# MICS-4514_CO_and_NOx_Sensor_Breakout.net
KiCad netlist of a schematic drawn in EAGLE
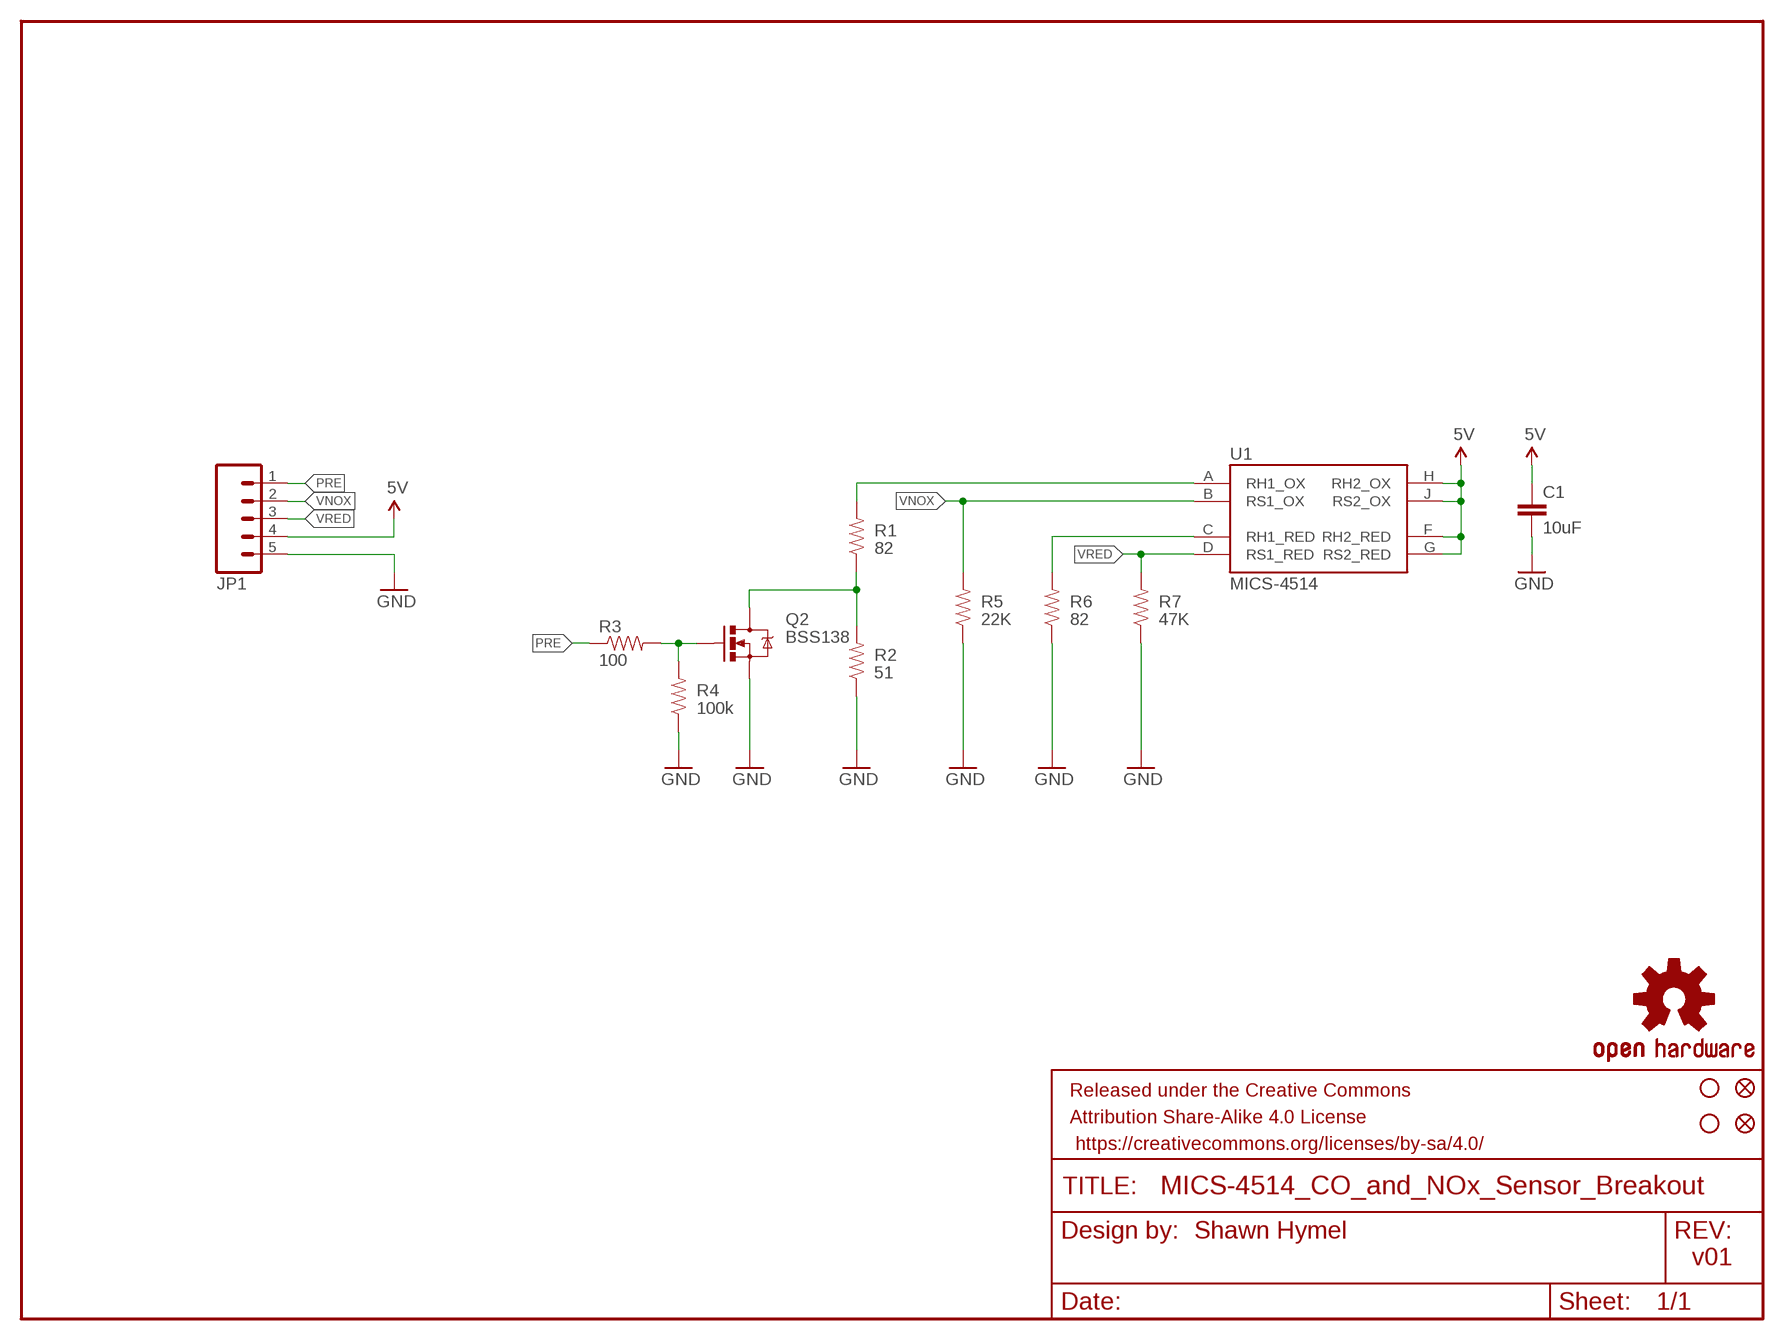
[diagram p0: schematic, sheet 1]

(export (version "E")
  (design (tool "Eeschema 10.0.6"))
  (components
    (comp (ref "C1")
      (value "10uF")
      (footprint "eagle-import:0805")
      (libsource (lib "eagle-import") (part "CAP0805"))
    )
    (comp (ref "FID1")
      (value "FIDUCIAL1X2")
      (footprint "eagle-import:FIDUCIAL-1X2")
      (libsource (lib "eagle-import") (part "FIDUCIAL1X2"))
    )
    (comp (ref "FID2")
      (value "FIDUCIAL1X2")
      (footprint "eagle-import:FIDUCIAL-1X2")
      (libsource (lib "eagle-import") (part "FIDUCIAL1X2"))
    )
    (comp (ref "FRAME1")
      (value "FRAME-LETTER")
      (footprint "eagle-import:CREATIVE_COMMONS")
      (libsource (lib "eagle-import") (part "FRAME-LETTER"))
    )
    (comp (ref "JP1")
      (value "M05LOCK")
      (footprint "eagle-import:1X05_LOCK")
      (libsource (lib "eagle-import") (part "M05LOCK"))
    )
    (comp (ref "LOGO1")
      (value "OSHW-LOGOS")
      (footprint "eagle-import:OSHW-LOGO-S")
      (libsource (lib "eagle-import") (part "OSHW-LOGOS"))
    )
    (comp (ref "Q2")
      (value "MOSFET-NCHANNELBSS138")
      (footprint "eagle-import:SOT23-3")
      (fields (field (name "P_NAME") "BSS138"))
      (libsource (lib "eagle-import") (part "MOSFET-NCHANNELBSS138"))
    )
    (comp (ref "R1")
      (value "82")
      (footprint "eagle-import:0805")
      (libsource (lib "eagle-import") (part "RESISTOR0805-RES"))
    )
    (comp (ref "R2")
      (value "51")
      (footprint "eagle-import:0603-RES")
      (libsource (lib "eagle-import") (part "RESISTOR0603"))
    )
    (comp (ref "R3")
      (value "100")
      (footprint "eagle-import:0603-RES")
      (libsource (lib "eagle-import") (part "100OHM1/10W1%(0603)"))
    )
    (comp (ref "R4")
      (value "100k")
      (footprint "eagle-import:0603-RES")
      (libsource (lib "eagle-import") (part "100KOHM1/10W1%(0603)"))
    )
    (comp (ref "R5")
      (value "22K")
      (footprint "eagle-import:0603-RES")
      (libsource (lib "eagle-import") (part "22KOHM1/10W1%(0603)"))
    )
    (comp (ref "R6")
      (value "82")
      (footprint "eagle-import:0805")
      (libsource (lib "eagle-import") (part "RESISTOR0805-RES"))
    )
    (comp (ref "R7")
      (value "47K")
      (footprint "eagle-import:0603-RES")
      (libsource (lib "eagle-import") (part "47KOHM1/10W1%(0603)"))
    )
    (comp (ref "STANDOFF3")
      (value "STAND-OFF")
      (footprint "eagle-import:STAND-OFF")
      (libsource (lib "eagle-import") (part "STAND-OFF"))
    )
    (comp (ref "STANDOFF5")
      (value "STAND-OFF")
      (footprint "eagle-import:STAND-OFF")
      (libsource (lib "eagle-import") (part "STAND-OFF"))
    )
    (comp (ref "U1")
      (value "MICS-4514")
      (footprint "eagle-import:MICS_10-SMD")
      (libsource (lib "eagle-import") (part "MICS-4514"))
    )
  )
  (nets
    (net (code "1") (name "5V") (class "Default")
      (node (ref "C1") (pin "1") (pinfunction "1_1") (pintype "passive"))
      (node (ref "JP1") (pin "4") (pinfunction "4_4") (pintype "passive"))
      (node (ref "U1") (pin "F") (pinfunction "RH2_RED_F") (pintype "bidirectional"))
      (node (ref "U1") (pin "G") (pinfunction "RS2_RED_G") (pintype "bidirectional"))
      (node (ref "U1") (pin "H") (pinfunction "RH2_OX_H") (pintype "bidirectional"))
      (node (ref "U1") (pin "J") (pinfunction "RS2_OX_J") (pintype "bidirectional"))
    )
    (net (code "2") (name "GND") (class "Default")
      (node (ref "C1") (pin "2") (pinfunction "2_2") (pintype "passive"))
      (node (ref "JP1") (pin "5") (pinfunction "5_5") (pintype "passive"))
      (node (ref "Q2") (pin "2") (pinfunction "S_2") (pintype "passive"))
      (node (ref "R2") (pin "1") (pinfunction "1_1") (pintype "passive"))
      (node (ref "R4") (pin "1") (pinfunction "1_1") (pintype "passive"))
      (node (ref "R5") (pin "1") (pinfunction "1_1") (pintype "passive"))
      (node (ref "R6") (pin "1") (pinfunction "1_1") (pintype "passive"))
      (node (ref "R7") (pin "1") (pinfunction "1_1") (pintype "passive"))
    )
    (net (code "3") (name "Net-(Q2-D)") (class "Default")
      (node (ref "Q2") (pin "3") (pinfunction "D_3") (pintype "passive"))
      (node (ref "R1") (pin "1") (pinfunction "1_1") (pintype "passive"))
      (node (ref "R2") (pin "2") (pinfunction "2_2") (pintype "passive"))
    )
    (net (code "4") (name "Net-(Q2-G)") (class "Default")
      (node (ref "Q2") (pin "1") (pinfunction "G_1") (pintype "passive"))
      (node (ref "R3") (pin "2") (pinfunction "2_2") (pintype "passive"))
      (node (ref "R4") (pin "2") (pinfunction "2_2") (pintype "passive"))
    )
    (net (code "5") (name "Net-(U1-RH1_OX)") (class "Default")
      (node (ref "R1") (pin "2") (pinfunction "2_2") (pintype "passive"))
      (node (ref "U1") (pin "A") (pinfunction "RH1_OX_A") (pintype "bidirectional"))
    )
    (net (code "6") (name "Net-(U1-RH1_RED)") (class "Default")
      (node (ref "R6") (pin "2") (pinfunction "2_2") (pintype "passive"))
      (node (ref "U1") (pin "C") (pinfunction "RH1_RED_C") (pintype "bidirectional"))
    )
    (net (code "7") (name "PRE") (class "Default")
      (node (ref "JP1") (pin "1") (pinfunction "1_1") (pintype "passive"))
      (node (ref "R3") (pin "1") (pinfunction "1_1") (pintype "passive"))
    )
    (net (code "8") (name "VNOX") (class "Default")
      (node (ref "JP1") (pin "2") (pinfunction "2_2") (pintype "passive"))
      (node (ref "R5") (pin "2") (pinfunction "2_2") (pintype "passive"))
      (node (ref "U1") (pin "B") (pinfunction "RS1_OX_B") (pintype "bidirectional"))
    )
    (net (code "9") (name "VRED") (class "Default")
      (node (ref "JP1") (pin "3") (pinfunction "3_3") (pintype "passive"))
      (node (ref "R7") (pin "2") (pinfunction "2_2") (pintype "passive"))
      (node (ref "U1") (pin "D") (pinfunction "RS1_RED_D") (pintype "bidirectional"))
    )
  )
)
